# LED_PROGECT_SCH.net
KiCad netlist of a schematic drawn in Altium Designer
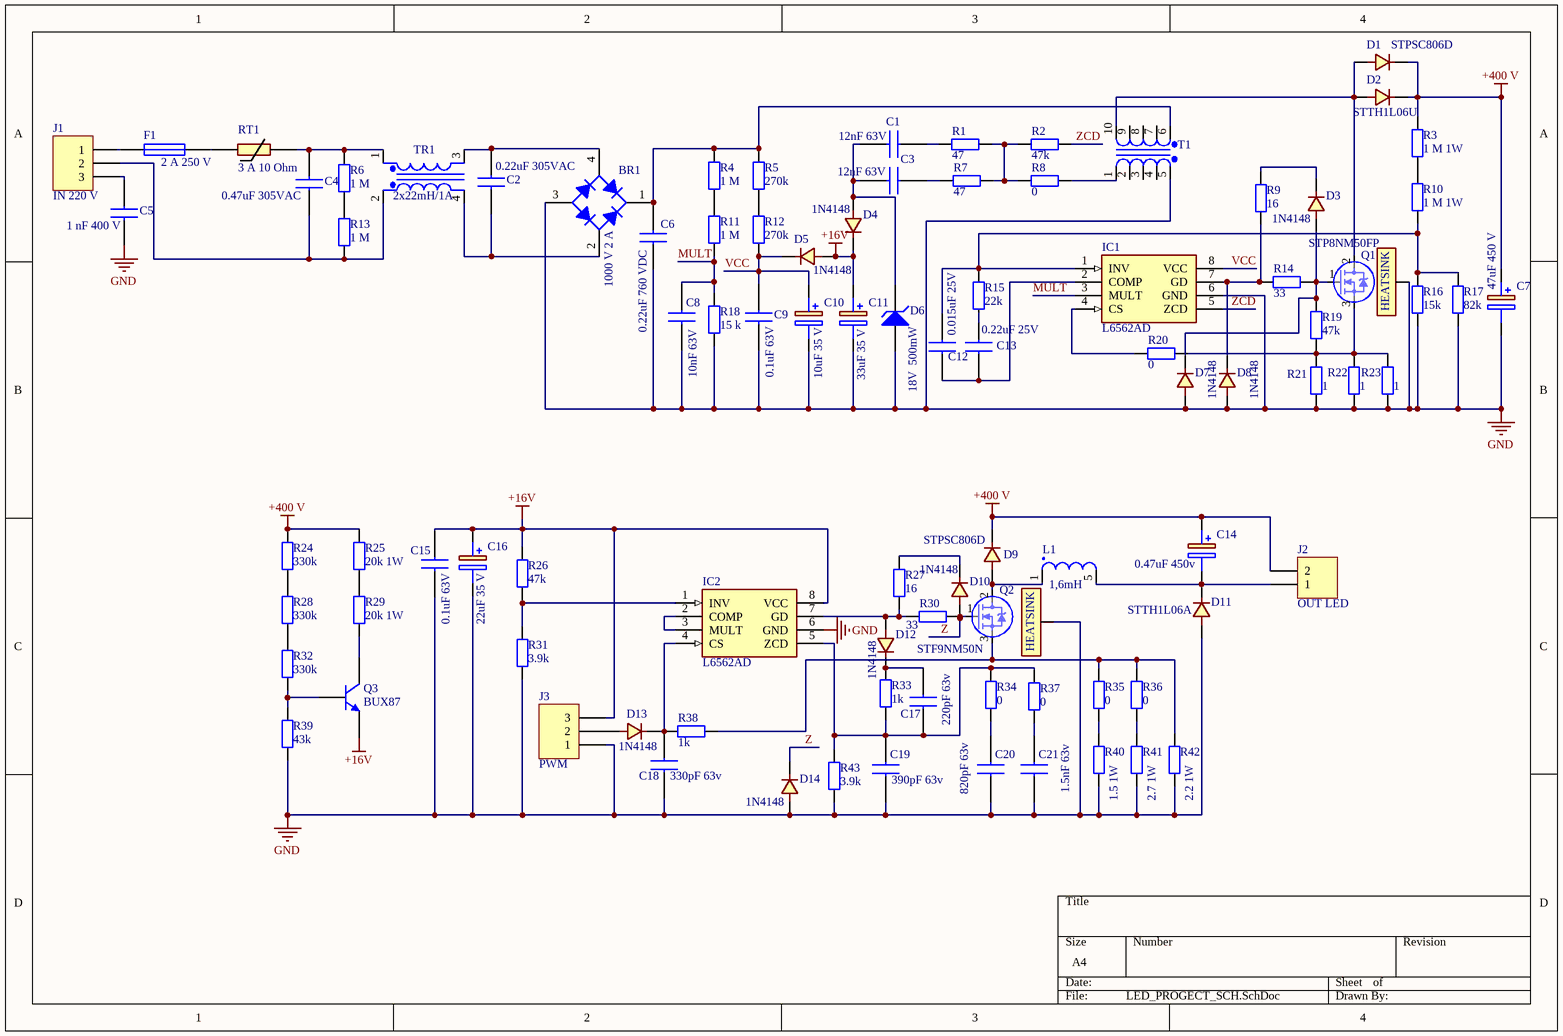
[diagram p0: LED_PROGECT_SCH.SchDoc]

(export (version "E")
  (design (tool "Eeschema 10.0.6"))
  (components
    (comp (ref "BR1")
      (value "1000 V 2 A")
      (footprint "SOPA-4")
      (description "Full Wave Diode Bridge")
      (fields (field (name "PUBLISHER") "Altium Limited"))
      (libsource (lib "Miscellaneous Devices") (part "Bridge1"))
    )
    (comp (ref "C1")
      (value "12nF 63V")
      (footprint "Cap1206")
      (description "Ceramic capacitor")
      (libsource (lib "SamacSys") (part "Capacotor 1206"))
    )
    (comp (ref "C2")
      (value "0.22uF 305VAC")
      (footprint "CAP32229")
      (description "Capacitor film")
      (libsource (lib "SamacSys") (part "Capacitor B32922"))
    )
    (comp (ref "C3")
      (value "12nF 63V")
      (footprint "Cap1206")
      (description "Ceramic capacitor")
      (libsource (lib "SamacSys") (part "Capacotor 1206"))
    )
    (comp (ref "C4")
      (value "0.47uF 305VAC")
      (footprint "CAP32229")
      (description "Capacitor film")
      (libsource (lib "SamacSys") (part "Capacitor B32922"))
    )
    (comp (ref "C5")
      (value "1 nF 400 V")
      (footprint "Capacitor radial")
      (description "Capacitor radial")
      (libsource (lib "SamacSys") (part "Capacitor C911U102MVWDBA7317"))
    )
    (comp (ref "C6")
      (value "0.22uF 760 VDC")
      (footprint "CAP32229")
      (description "Capacitor film")
      (libsource (lib "SamacSys") (part "Capacitor B32922"))
    )
    (comp (ref "C7")
      (value "47uF 450 V")
      (footprint "CAP ALUMINIUM 16 mm 1")
      (description "Cap polarized")
      (libsource (lib "SamacSys") (part "CAP POLARIZES 16-31 mm"))
    )
    (comp (ref "C8")
      (value "10nF 63V")
      (footprint "Cap1206")
      (description "Ceramic capacitor")
      (libsource (lib "SamacSys") (part "Capacotor 1206"))
    )
    (comp (ref "C9")
      (value "0.1uF 63V")
      (footprint "Cap1206")
      (description "Ceramic capacitor")
      (libsource (lib "SamacSys") (part "Capacotor 1206"))
    )
    (comp (ref "C10")
      (value "10uF 35 V")
      (footprint "CAP ALUM 5mm")
      (description "Cap polarized")
      (libsource (lib "SamacSys") (part "CAP POLARIZES 5-2 mm"))
    )
    (comp (ref "C11")
      (value "33uF 35 V")
      (footprint "CAP ALUM 5mm")
      (description "Cap polarized")
      (libsource (lib "SamacSys") (part "CAP POLARIZES 5-2 mm"))
    )
    (comp (ref "C12")
      (value "0.015uF 25V")
      (footprint "Cap1206")
      (description "Ceramic capacitor")
      (libsource (lib "SamacSys") (part "Capacotor 1206"))
    )
    (comp (ref "C13")
      (value "0.22uF 25V")
      (footprint "Cap1206")
      (description "Ceramic capacitor")
      (libsource (lib "SamacSys") (part "Capacotor 1206"))
    )
    (comp (ref "C14")
      (value "0.47uF 450v")
      (footprint "Cap aluminium 12.5x5")
      (description "Capacitpr polarized")
      (libsource (lib "SamacSys") (part "ESMG451ELLR47MJC5S"))
    )
    (comp (ref "C15")
      (value "0.1uF 63V")
      (footprint "Cap1206")
      (description "Ceramic capacitor")
      (libsource (lib "SamacSys") (part "Capacotor 1206"))
    )
    (comp (ref "C16")
      (value "22uF 35 V")
      (footprint "CAP ALUM 5mm")
      (description "Cap polarized")
      (libsource (lib "SamacSys") (part "CAP POLARIZES 5-2 mm"))
    )
    (comp (ref "C17")
      (value "220pF 63v")
      (footprint "CAP0805")
      (description "Ceramic capacitor")
      (libsource (lib "SamacSys") (part "Capacotor ceramic"))
    )
    (comp (ref "C18")
      (value "330pF 63v")
      (footprint "Cap1206")
      (description "Ceramic capacitor")
      (libsource (lib "SamacSys") (part "Capacotor 1206"))
    )
    (comp (ref "C19")
      (value "390pF 63v")
      (footprint "Cap1206")
      (description "Ceramic capacitor")
      (libsource (lib "SamacSys") (part "Capacotor 1206"))
    )
    (comp (ref "C20")
      (value "820pF 63v")
      (footprint "Cap1206")
      (description "Ceramic capacitor")
      (libsource (lib "SamacSys") (part "Capacotor 1206"))
    )
    (comp (ref "C21")
      (value "1.5nF 63v")
      (footprint "Cap1206")
      (description "Ceramic capacitor")
      (libsource (lib "SamacSys") (part "Capacotor 1206"))
    )
    (comp (ref "D1")
      (value "STPSC806D")
      (footprint "TO220 DOIDE")
      (description "600 V, 5 A")
      (libsource (lib "SamacSys") (part "STPSC806D"))
    )
    (comp (ref "D2")
      (value "STTH1L06U")
      (footprint "SMB")
      (description "600 V 1 A")
      (libsource (lib "SamacSys") (part "STTH1L06U"))
    )
    (comp (ref "D3")
      (value "1N4148")
      (footprint "SOD123")
      (description "Diode")
      (libsource (lib "SamacSys") (part "1N4148"))
    )
    (comp (ref "D4")
      (value "1N4148")
      (footprint "SOD123")
      (description "Diode")
      (libsource (lib "SamacSys") (part "1N4148"))
    )
    (comp (ref "D5")
      (value "1N4148")
      (footprint "SOD123")
      (description "Diode")
      (libsource (lib "SamacSys") (part "1N4148"))
    )
    (comp (ref "D6")
      (value "18V  500mW")
      (footprint "SOD123")
      (description "Diode Zener")
      (libsource (lib "SamacSys") (part "BZT52C18-7-F"))
    )
    (comp (ref "D7")
      (value "1N4148")
      (footprint "SOD123")
      (description "Diode")
      (libsource (lib "SamacSys") (part "1N4148"))
    )
    (comp (ref "D8")
      (value "1N4148")
      (footprint "SOD123")
      (description "Diode")
      (libsource (lib "SamacSys") (part "1N4148"))
    )
    (comp (ref "D9")
      (value "STPSC806D")
      (footprint "TO220 DOIDE")
      (description "600 V, 5 A")
      (libsource (lib "SamacSys") (part "STPSC806D"))
    )
    (comp (ref "D10")
      (value "1N4148")
      (footprint "SOD123")
      (description "Diode")
      (libsource (lib "SamacSys") (part "1N4148"))
    )
    (comp (ref "D11")
      (value "STTH1L06A")
      (footprint "SMA")
      (description "600 V ,1 A")
      (libsource (lib "SamacSys") (part "STTH1L06A"))
    )
    (comp (ref "D12")
      (value "1N4148")
      (footprint "SOD123")
      (description "Diode")
      (libsource (lib "SamacSys") (part "1N4148"))
    )
    (comp (ref "D13")
      (value "1N4148")
      (footprint "SOD123")
      (description "Diode")
      (libsource (lib "SamacSys") (part "1N4148"))
    )
    (comp (ref "D14")
      (value "1N4148")
      (footprint "SOD123")
      (description "Diode")
      (libsource (lib "SamacSys") (part "1N4148"))
    )
    (comp (ref "F1")
      (value "2 A 250 V")
      (footprint "FUSE SMD")
      (description "Fuse")
      (fields (field (name "PUBLISHER") "Altium Limited"))
      (libsource (lib "Miscellaneous Devices") (part "Fuse 1"))
    )
    (comp (ref "H1") (value "HEATSINK") (footprint "HEATSINK") (libsource (lib "SamacSys") (part "HEATSINK")))
    (comp (ref "H2") (value "HEATSINK") (footprint "HEATSINK") (libsource (lib "SamacSys") (part "HEATSINK")))
    (comp (ref "IC1")
      (value "L6562AD")
      (footprint "SOIC127P600X175-8N")
      (libsource (lib "SamacSys") (part "L6562AD"))
    )
    (comp (ref "IC2")
      (value "L6562AD")
      (footprint "SOIC127P600X175-8N")
      (libsource (lib "SamacSys") (part "L6562AD"))
    )
    (comp (ref "J1")
      (value "IN 220 V")
      (footprint "PIN3 TERMINAL")
      (libsource (lib "") (part "PIN3 TERMINAL 5 mm_1"))
    )
    (comp (ref "J2")
      (value "OUT LED")
      (footprint "TERMINAL 2 PIN")
      (libsource (lib "Miscellaneous Connectors") (part "PIN 2 TERMINAL"))
    )
    (comp (ref "J3")
      (value "PWM")
      (footprint "PIN3 TERMINAL")
      (libsource (lib "Miscellaneous Connectors") (part "PIN3 TERMINAL 5 mm"))
    )
    (comp (ref "L1")
      (value "1,6mH")
      (footprint "INDUCTOR E25/13/7")
      (description "INDUCTOR")
      (libsource (lib "Miscellaneous Devices") (part "INDUCTOR E25/13/7"))
    )
    (comp (ref "Q1")
      (value "STP8NM50FP")
      (footprint "TO220")
      (description "N-channel 500 V, 0.73 Ω typ., 5 A")
      (libsource (lib "SamacSys") (part "STD8NM50N"))
    )
    (comp (ref "Q2")
      (value "STF9NM50N")
      (footprint "TO220")
      (description "N-channel 500 V, 0.73 Ω typ., 5 A")
      (libsource (lib "SamacSys") (part "STD8NM50N"))
    )
    (comp (ref "Q3")
      (value "BUX87")
      (footprint "SOT32")
      (description "NPN power transistor")
      (libsource (lib "SamacSys") (part "BUX87"))
    )
    (comp (ref "R1")
      (value "47")
      (footprint "RES1206")
      (description "Resistor 1206")
      (libsource (lib "") (part "RES1206_2"))
    )
    (comp (ref "R2")
      (value "47k")
      (footprint "RES1206")
      (description "Resistor 1206")
      (libsource (lib "") (part "RES1206_2"))
    )
    (comp (ref "R3")
      (value "1 M 1W")
      (footprint "AXIAL-0.6")
      (description "Resistor")
      (fields (field (name "PUBLISHER") "Altium Limited"))
      (libsource (lib "Miscellaneous Devices") (part "Res 1W"))
    )
    (comp (ref "R4")
      (value "1 M")
      (footprint "RES1206")
      (description "Resistor 1206")
      (libsource (lib "") (part "RES1206_1"))
    )
    (comp (ref "R5")
      (value "270k")
      (footprint "RES1206")
      (description "Resistor 1206")
      (libsource (lib "") (part "RES1206_1"))
    )
    (comp (ref "R6")
      (value "1 M")
      (footprint "RES1206")
      (description "Resistor 1206")
      (libsource (lib "") (part "RES1206_1"))
    )
    (comp (ref "R7")
      (value "47")
      (footprint "RES1206")
      (description "Resistor 1206")
      (libsource (lib "") (part "RES1206_2"))
    )
    (comp (ref "R8")
      (value "0")
      (footprint "RES1206")
      (description "Resistor 1206")
      (libsource (lib "") (part "RES1206_2"))
    )
    (comp (ref "R9")
      (value "16")
      (footprint "RES1206")
      (description "Resistor 1206")
      (libsource (lib "") (part "RES1206_1"))
    )
    (comp (ref "R10")
      (value "1 M 1W")
      (footprint "AXIAL-0.6")
      (description "Resistor")
      (fields (field (name "PUBLISHER") "Altium Limited"))
      (libsource (lib "Miscellaneous Devices") (part "Res 1W"))
    )
    (comp (ref "R11")
      (value "1 M")
      (footprint "RES1206")
      (description "Resistor 1206")
      (libsource (lib "") (part "RES1206_1"))
    )
    (comp (ref "R12")
      (value "270k")
      (footprint "RES1206")
      (description "Resistor 1206")
      (libsource (lib "") (part "RES1206_1"))
    )
    (comp (ref "R13")
      (value "1 M")
      (footprint "RES1206")
      (description "Resistor 1206")
      (libsource (lib "") (part "RES1206_1"))
    )
    (comp (ref "R14")
      (value "33")
      (footprint "RES1206")
      (description "Resistor 1206")
      (libsource (lib "") (part "RES1206_3"))
    )
    (comp (ref "R15")
      (value "22k")
      (footprint "RES1206")
      (description "Resistor 1206")
      (libsource (lib "Miscellaneous Devices") (part "RES1206"))
    )
    (comp (ref "R16")
      (value "15k")
      (footprint "RES1206")
      (description "Resistor 1206")
      (libsource (lib "Miscellaneous Devices") (part "RES1206"))
    )
    (comp (ref "R17")
      (value "82k")
      (footprint "RES1206")
      (description "Resistor 1206")
      (libsource (lib "Miscellaneous Devices") (part "RES1206"))
    )
    (comp (ref "R18")
      (value "15 k")
      (footprint "RES1206")
      (description "Resistor 1206")
      (libsource (lib "") (part "RES1206_1"))
    )
    (comp (ref "R19")
      (value "47k")
      (footprint "RES1206")
      (description "Resistor 1206")
      (libsource (lib "") (part "RES1206_1"))
    )
    (comp (ref "R20")
      (value "0")
      (footprint "RES1206")
      (description "Resistor 1206")
      (libsource (lib "") (part "RES1206_2"))
    )
    (comp (ref "R21")
      (value "1")
      (footprint "RES1206")
      (description "Resistor 1206")
      (libsource (lib "") (part "RES1206_1"))
    )
    (comp (ref "R22")
      (value "1")
      (footprint "RES1206")
      (description "Resistor 1206")
      (libsource (lib "") (part "RES1206_1"))
    )
    (comp (ref "R23")
      (value "1")
      (footprint "RES1206")
      (description "Resistor 1206")
      (libsource (lib "") (part "RES1206_1"))
    )
    (comp (ref "R24")
      (value "330k")
      (footprint "RES1206")
      (description "Resistor 1206")
      (libsource (lib "") (part "RES1206_1"))
    )
    (comp (ref "R25")
      (value "20k 1W")
      (footprint "AXIAL-0.6")
      (description "Resistor")
      (fields (field (name "PUBLISHER") "Altium Limited"))
      (libsource (lib "Miscellaneous Devices") (part "Res 1W"))
    )
    (comp (ref "R26")
      (value "47k")
      (footprint "RES1206")
      (description "Resistor 1206")
      (libsource (lib "") (part "RES1206_1"))
    )
    (comp (ref "R27")
      (value "16")
      (footprint "RES1206")
      (description "Resistor 1206")
      (libsource (lib "") (part "RES1206_1"))
    )
    (comp (ref "R28")
      (value "330k")
      (footprint "RES1206")
      (description "Resistor 1206")
      (libsource (lib "") (part "RES1206_1"))
    )
    (comp (ref "R29")
      (value "20k 1W")
      (footprint "AXIAL-0.6")
      (description "Resistor")
      (fields (field (name "PUBLISHER") "Altium Limited"))
      (libsource (lib "Miscellaneous Devices") (part "Res 1W"))
    )
    (comp (ref "R30")
      (value "33")
      (footprint "RES1206")
      (description "Resistor 1206")
      (libsource (lib "") (part "RES1206_2"))
    )
    (comp (ref "R31")
      (value "3.9k")
      (footprint "RES1206")
      (description "Resistor 1206")
      (libsource (lib "") (part "RES1206_1"))
    )
    (comp (ref "R32")
      (value "330k")
      (footprint "RES1206")
      (description "Resistor 1206")
      (libsource (lib "") (part "RES1206_1"))
    )
    (comp (ref "R33")
      (value "1k")
      (footprint "RES1206")
      (description "Resistor 1206")
      (libsource (lib "Miscellaneous Devices") (part "RES1206"))
    )
    (comp (ref "R34")
      (value "0")
      (footprint "RES1206")
      (description "Resistor 1206")
      (libsource (lib "Miscellaneous Devices") (part "RES1206"))
    )
    (comp (ref "R35")
      (value "0")
      (footprint "RES1206")
      (description "Resistor 1206")
      (libsource (lib "Miscellaneous Devices") (part "RES1206"))
    )
    (comp (ref "R36")
      (value "0")
      (footprint "RES1206")
      (description "Resistor 1206")
      (libsource (lib "Miscellaneous Devices") (part "RES1206"))
    )
    (comp (ref "R37")
      (value "0")
      (footprint "RES1206")
      (description "Resistor 1206")
      (libsource (lib "Miscellaneous Devices") (part "RES1206"))
    )
    (comp (ref "R38")
      (value "1k")
      (footprint "RES1206")
      (description "Resistor 1206")
      (libsource (lib "") (part "RES1206_2"))
    )
    (comp (ref "R39")
      (value "43k")
      (footprint "RES1206")
      (description "Resistor 1206")
      (libsource (lib "") (part "RES1206_1"))
    )
    (comp (ref "R40")
      (value "1.5 1W")
      (footprint "AXIAL-0.6")
      (description "Resistor")
      (fields (field (name "PUBLISHER") "Altium Limited"))
      (libsource (lib "Miscellaneous Devices") (part "Res 1W"))
    )
    (comp (ref "R41")
      (value "2.7 1W")
      (footprint "AXIAL-0.6")
      (description "Resistor")
      (fields (field (name "PUBLISHER") "Altium Limited"))
      (libsource (lib "Miscellaneous Devices") (part "Res 1W"))
    )
    (comp (ref "R42")
      (value "2.2 1W")
      (footprint "AXIAL-0.6")
      (description "Resistor")
      (fields (field (name "PUBLISHER") "Altium Limited"))
      (libsource (lib "Miscellaneous Devices") (part "Res 1W"))
    )
    (comp (ref "R43")
      (value "3.9k")
      (footprint "RES1206")
      (description "Resistor 1206")
      (libsource (lib "Miscellaneous Devices") (part "RES1206"))
    )
    (comp (ref "RT1")
      (value "3 A 10 Ohm")
      (footprint "NTC")
      (description "Thermistor")
      (fields
        (field (name "MANUFACTURER_PART_NUMBER") "B57235S0100M051")
        (field (name "MOUSER PART NUMBER") "871-B57235S0100M051")
      )
      (libsource (lib "SamacSys") (part "B57235S0100M051"))
    )
    (comp (ref "T1")
      (value "Trans E25/13/7")
      (footprint "TRANS E25/13/7")
      (description "Center-Tapped Transformer (Coupled Inductor Model)")
      (fields (field (name "PUBLISHER") "Altium Limited"))
      (libsource (lib "Miscellaneous Devices") (part "Trans E25/13/7"))
    )
    (comp (ref "TR1")
      (value "2x22mH/1A")
      (footprint "CHOKE IND")
      (description "CHOKE")
      (libsource (lib "Miscellaneous Devices") (part "CHOKES 22uH 1A"))
    )
  )
  (nets
    (net (code "1") (name "+16V") (class "Default")
      (node (ref "C11") (pin "1") (pinfunction "+_1") (pintype "passive"))
      (node (ref "C15") (pin "2") (pinfunction "2_2") (pintype "passive"))
      (node (ref "C16") (pin "1") (pinfunction "+_1") (pintype "passive"))
      (node (ref "D4") (pin "2") (pinfunction "2_2") (pintype "passive"))
      (node (ref "D5") (pin "1") (pinfunction "1_1") (pintype "passive"))
      (node (ref "IC2") (pin "8") (pinfunction "VCC_8") (pintype "power_in"))
      (node (ref "J3") (pin "3") (pinfunction "3_3") (pintype "passive"))
      (node (ref "Q3") (pin "1") (pinfunction "E_1") (pintype "passive"))
      (node (ref "R26") (pin "2") (pinfunction "2_2") (pintype "passive"))
    )
    (net (code "2") (name "+400 V") (class "Default")
      (node (ref "C14") (pin "1") (pinfunction "+_1") (pintype "passive"))
      (node (ref "C7") (pin "1") (pinfunction "1_1") (pintype "passive"))
      (node (ref "D1") (pin "1") (pinfunction "1_1") (pintype "passive"))
      (node (ref "D2") (pin "2") (pinfunction "2_2") (pintype "passive"))
      (node (ref "D9") (pin "1") (pinfunction "1_1") (pintype "passive"))
      (node (ref "J2") (pin "2") (pinfunction "2_2") (pintype "passive"))
      (node (ref "R24") (pin "2") (pinfunction "2_2") (pintype "passive"))
      (node (ref "R25") (pin "2") (pinfunction "2_2") (pintype "passive"))
      (node (ref "R3") (pin "2") (pinfunction "2_2") (pintype "passive"))
    )
    (net (code "3") (name "/MULT") (class "Default")
      (node (ref "C8") (pin "2") (pinfunction "2_2") (pintype "passive"))
      (node (ref "IC1") (pin "3") (pinfunction "MULT_3") (pintype "passive"))
      (node (ref "R11") (pin "1") (pinfunction "1_1") (pintype "passive"))
      (node (ref "R18") (pin "2") (pinfunction "2_2") (pintype "passive"))
    )
    (net (code "4") (name "/VCC") (class "Default")
      (node (ref "C10") (pin "1") (pinfunction "+_1") (pintype "passive"))
      (node (ref "C9") (pin "2") (pinfunction "2_2") (pintype "passive"))
      (node (ref "D5") (pin "2") (pinfunction "2_2") (pintype "passive"))
      (node (ref "IC1") (pin "8") (pinfunction "VCC_8") (pintype "power_in"))
      (node (ref "R12") (pin "1") (pinfunction "1_1") (pintype "passive"))
    )
    (net (code "5") (name "/Z") (class "Default")
      (node (ref "D10") (pin "1") (pinfunction "1_1") (pintype "passive"))
      (node (ref "D14") (pin "2") (pinfunction "2_2") (pintype "passive"))
      (node (ref "Q2") (pin "1") (pinfunction "G_1") (pintype "passive"))
      (node (ref "R30") (pin "1") (pinfunction "1_1") (pintype "passive"))
    )
    (net (code "6") (name "/ZCD") (class "Default")
      (node (ref "IC1") (pin "5") (pinfunction "ZCD_5") (pintype "passive"))
      (node (ref "R2") (pin "1") (pinfunction "1_1") (pintype "passive"))
    )
    (net (code "7") (name "GND") (class "Default")
      (node (ref "BR1") (pin "3") (pinfunction "A_3") (pintype "passive"))
      (node (ref "C10") (pin "2") (pinfunction "-_2") (pintype "passive"))
      (node (ref "C11") (pin "2") (pinfunction "-_2") (pintype "passive"))
      (node (ref "C15") (pin "1") (pinfunction "1_1") (pintype "passive"))
      (node (ref "C16") (pin "2") (pinfunction "-_2") (pintype "passive"))
      (node (ref "C18") (pin "1") (pinfunction "1_1") (pintype "passive"))
      (node (ref "C19") (pin "1") (pinfunction "1_1") (pintype "passive"))
      (node (ref "C20") (pin "1") (pinfunction "1_1") (pintype "passive"))
      (node (ref "C21") (pin "1") (pinfunction "1_1") (pintype "passive"))
      (node (ref "C5") (pin "1") (pinfunction "1_1") (pintype "passive"))
      (node (ref "C6") (pin "1") (pinfunction "1_1") (pintype "passive"))
      (node (ref "C7") (pin "2") (pinfunction "2_2") (pintype "passive"))
      (node (ref "C8") (pin "1") (pinfunction "1_1") (pintype "passive"))
      (node (ref "C9") (pin "1") (pinfunction "1_1") (pintype "passive"))
      (node (ref "D11") (pin "1") (pinfunction "1_1") (pintype "passive"))
      (node (ref "D14") (pin "1") (pinfunction "1_1") (pintype "passive"))
      (node (ref "D6") (pin "1") (pinfunction "A_1") (pintype "passive"))
      (node (ref "D7") (pin "1") (pinfunction "1_1") (pintype "passive"))
      (node (ref "D8") (pin "1") (pinfunction "1_1") (pintype "passive"))
      (node (ref "H1") (pin "1") (pinfunction "C_1") (pintype "power_in"))
      (node (ref "H2") (pin "1") (pinfunction "C_1") (pintype "power_in"))
      (node (ref "IC1") (pin "6") (pinfunction "GND_6") (pintype "power_in"))
      (node (ref "IC2") (pin "6") (pinfunction "GND_6") (pintype "power_in"))
      (node (ref "J3") (pin "1") (pinfunction "1_1") (pintype "passive"))
      (node (ref "R16") (pin "2") (pinfunction "2_2") (pintype "passive"))
      (node (ref "R17") (pin "2") (pinfunction "2_2") (pintype "passive"))
      (node (ref "R18") (pin "1") (pinfunction "1_1") (pintype "passive"))
      (node (ref "R21") (pin "1") (pinfunction "1_1") (pintype "passive"))
      (node (ref "R22") (pin "1") (pinfunction "1_1") (pintype "passive"))
      (node (ref "R23") (pin "1") (pinfunction "1_1") (pintype "passive"))
      (node (ref "R31") (pin "1") (pinfunction "1_1") (pintype "passive"))
      (node (ref "R39") (pin "1") (pinfunction "1_1") (pintype "passive"))
      (node (ref "R40") (pin "1") (pinfunction "1_1") (pintype "passive"))
      (node (ref "R41") (pin "1") (pinfunction "1_1") (pintype "passive"))
      (node (ref "R42") (pin "1") (pinfunction "1_1") (pintype "passive"))
      (node (ref "R43") (pin "2") (pinfunction "2_2") (pintype "passive"))
      (node (ref "T1") (pin "5") (pinfunction "5_5") (pintype "passive"))
    )
    (net (code "8") (name "Net-(BR1-K)") (class "Default")
      (node (ref "BR1") (pin "1") (pinfunction "K_1") (pintype "passive"))
      (node (ref "C6") (pin "2") (pinfunction "2_2") (pintype "passive"))
      (node (ref "R4") (pin "2") (pinfunction "2_2") (pintype "passive"))
      (node (ref "R5") (pin "2") (pinfunction "2_2") (pintype "passive"))
      (node (ref "T1") (pin "6") (pinfunction "6_6") (pintype "passive"))
    )
    (net (code "9") (name "Net-(C1-Pad1)") (class "Default")
      (node (ref "C1") (pin "1") (pinfunction "1_1") (pintype "passive"))
      (node (ref "R1") (pin "2") (pinfunction "2_2") (pintype "passive"))
    )
    (net (code "10") (name "Net-(C3-Pad1)") (class "Default")
      (node (ref "C3") (pin "1") (pinfunction "1_1") (pintype "passive"))
      (node (ref "R7") (pin "2") (pinfunction "2_2") (pintype "passive"))
    )
    (net (code "11") (name "Net-(C5-Pad2)") (class "Default")
      (node (ref "C5") (pin "2") (pinfunction "2_2") (pintype "passive"))
      (node (ref "J1") (pin "3") (pinfunction "3_3") (pintype "passive"))
    )
    (net (code "12") (name "Net-(C13-Pad1)") (class "Default")
      (node (ref "C13") (pin "1") (pinfunction "1_1") (pintype "passive"))
      (node (ref "R15") (pin "2") (pinfunction "2_2") (pintype "passive"))
    )
    (net (code "13") (name "Net-(C14--)") (class "Default")
      (node (ref "C14") (pin "2") (pinfunction "-_2") (pintype "passive"))
      (node (ref "D11") (pin "2") (pinfunction "2_2") (pintype "passive"))
      (node (ref "J2") (pin "1") (pinfunction "1_1") (pintype "passive"))
      (node (ref "L1") (pin "5") (pinfunction "5_5") (pintype "passive"))
    )
    (net (code "14") (name "Net-(C17-Pad2)") (class "Default")
      (node (ref "C17") (pin "2") (pinfunction "2_2") (pintype "passive"))
      (node (ref "D12") (pin "2") (pinfunction "2_2") (pintype "passive"))
      (node (ref "R33") (pin "1") (pinfunction "1_1") (pintype "passive"))
    )
    (net (code "15") (name "Net-(C20-Pad2)") (class "Default")
      (node (ref "C20") (pin "2") (pinfunction "2_2") (pintype "passive"))
      (node (ref "R34") (pin "2") (pinfunction "2_2") (pintype "passive"))
    )
    (net (code "16") (name "Net-(C21-Pad2)") (class "Default")
      (node (ref "C21") (pin "2") (pinfunction "2_2") (pintype "passive"))
      (node (ref "R37") (pin "2") (pinfunction "2_2") (pintype "passive"))
    )
    (net (code "17") (name "Net-(D3-Pad2)") (class "Default")
      (node (ref "D3") (pin "2") (pinfunction "2_2") (pintype "passive"))
      (node (ref "R9") (pin "2") (pinfunction "2_2") (pintype "passive"))
    )
    (net (code "18") (name "Net-(D6-K)") (class "Default")
      (node (ref "C1") (pin "2") (pinfunction "2_2") (pintype "passive"))
      (node (ref "C3") (pin "2") (pinfunction "2_2") (pintype "passive"))
      (node (ref "D4") (pin "1") (pinfunction "1_1") (pintype "passive"))
      (node (ref "D6") (pin "2") (pinfunction "K_2") (pintype "passive"))
    )
    (net (code "19") (name "Net-(D10-Pad2)") (class "Default")
      (node (ref "D10") (pin "2") (pinfunction "2_2") (pintype "passive"))
      (node (ref "R27") (pin "2") (pinfunction "2_2") (pintype "passive"))
    )
    (net (code "20") (name "Net-(D13-Pad1)") (class "Default")
      (node (ref "D13") (pin "1") (pinfunction "1_1") (pintype "passive"))
      (node (ref "J3") (pin "2") (pinfunction "2_2") (pintype "passive"))
    )
    (net (code "21") (name "Net-(F1-Pad1)") (class "Default")
      (node (ref "F1") (pin "1") (pinfunction "1_1") (pintype "passive"))
      (node (ref "J1") (pin "1") (pinfunction "1_1") (pintype "passive"))
    )
    (net (code "22") (name "Net-(F1-Pad2)") (class "Default")
      (node (ref "F1") (pin "2") (pinfunction "2_2") (pintype "passive"))
      (node (ref "RT1") (pin "1") (pinfunction "1_1") (pintype "passive"))
    )
    (net (code "23") (name "Net-(IC1-COMP)") (class "Default")
      (node (ref "C12") (pin "2") (pinfunction "2_2") (pintype "passive"))
      (node (ref "C13") (pin "2") (pinfunction "2_2") (pintype "passive"))
      (node (ref "IC1") (pin "2") (pinfunction "COMP_2") (pintype "passive"))
    )
    (net (code "24") (name "Net-(IC1-CS)") (class "Default")
      (node (ref "IC1") (pin "4") (pinfunction "CS_4") (pintype "input"))
      (node (ref "R20") (pin "2") (pinfunction "2_2") (pintype "passive"))
    )
    (net (code "25") (name "Net-(IC1-GD)") (class "Default")
      (node (ref "D8") (pin "2") (pinfunction "2_2") (pintype "passive"))
      (node (ref "IC1") (pin "7") (pinfunction "GD_7") (pintype "passive"))
      (node (ref "R14") (pin "1") (pinfunction "1_1") (pintype "passive"))
      (node (ref "R9") (pin "1") (pinfunction "1_1") (pintype "passive"))
    )
    (net (code "26") (name "Net-(IC1-INV)") (class "Default")
      (node (ref "C12") (pin "1") (pinfunction "1_1") (pintype "passive"))
      (node (ref "IC1") (pin "1") (pinfunction "INV_1") (pintype "input"))
      (node (ref "R10") (pin "1") (pinfunction "1_1") (pintype "passive"))
      (node (ref "R15") (pin "1") (pinfunction "1_1") (pintype "passive"))
      (node (ref "R16") (pin "1") (pinfunction "1_1") (pintype "passive"))
      (node (ref "R17") (pin "1") (pinfunction "1_1") (pintype "passive"))
    )
    (net (code "27") (name "Net-(IC2-COMP)") (class "Default")
      (node (ref "IC2") (pin "2") (pinfunction "COMP_2") (pintype "passive"))
      (node (ref "IC2") (pin "3") (pinfunction "MULT_3") (pintype "passive"))
    )
    (net (code "28") (name "Net-(IC2-CS)") (class "Default")
      (node (ref "C18") (pin "2") (pinfunction "2_2") (pintype "passive"))
      (node (ref "D13") (pin "2") (pinfunction "2_2") (pintype "passive"))
      (node (ref "IC2") (pin "4") (pinfunction "CS_4") (pintype "input"))
      (node (ref "R38") (pin "2") (pinfunction "2_2") (pintype "passive"))
    )
    (net (code "29") (name "Net-(IC2-GD)") (class "Default")
      (node (ref "D12") (pin "1") (pinfunction "1_1") (pintype "passive"))
      (node (ref "IC2") (pin "7") (pinfunction "GD_7") (pintype "passive"))
      (node (ref "R27") (pin "1") (pinfunction "1_1") (pintype "passive"))
      (node (ref "R30") (pin "2") (pinfunction "2_2") (pintype "passive"))
    )
    (net (code "30") (name "Net-(IC2-INV)") (class "Default")
      (node (ref "IC2") (pin "1") (pinfunction "INV_1") (pintype "input"))
      (node (ref "R26") (pin "1") (pinfunction "1_1") (pintype "passive"))
      (node (ref "R31") (pin "2") (pinfunction "2_2") (pintype "passive"))
    )
    (net (code "31") (name "Net-(IC2-ZCD)") (class "Default")
      (node (ref "C17") (pin "1") (pinfunction "1_1") (pintype "passive"))
      (node (ref "C19") (pin "2") (pinfunction "2_2") (pintype "passive"))
      (node (ref "IC2") (pin "5") (pinfunction "ZCD_5") (pintype "passive"))
      (node (ref "R33") (pin "2") (pinfunction "2_2") (pintype "passive"))
      (node (ref "R34") (pin "1") (pinfunction "1_1") (pintype "passive"))
      (node (ref "R37") (pin "1") (pinfunction "1_1") (pintype "passive"))
      (node (ref "R43") (pin "1") (pinfunction "1_1") (pintype "passive"))
    )
    (net (code "32") (name "Net-(Q1-D)") (class "Default")
      (node (ref "D1") (pin "2") (pinfunction "2_2") (pintype "passive"))
      (node (ref "D2") (pin "1") (pinfunction "1_1") (pintype "passive"))
      (node (ref "Q1") (pin "2") (pinfunction "D_2") (pintype "passive"))
      (node (ref "T1") (pin "10") (pinfunction "10_10") (pintype "passive"))
    )
    (net (code "33") (name "Net-(Q1-G)") (class "Default")
      (node (ref "D3") (pin "1") (pinfunction "1_1") (pintype "passive"))
      (node (ref "D7") (pin "2") (pinfunction "2_2") (pintype "passive"))
      (node (ref "Q1") (pin "1") (pinfunction "G_1") (pintype "passive"))
      (node (ref "R14") (pin "2") (pinfunction "2_2") (pintype "passive"))
      (node (ref "R19") (pin "2") (pinfunction "2_2") (pintype "passive"))
    )
    (net (code "34") (name "Net-(Q1-S)") (class "Default")
      (node (ref "Q1") (pin "3") (pinfunction "S_3") (pintype "passive"))
      (node (ref "R19") (pin "1") (pinfunction "1_1") (pintype "passive"))
      (node (ref "R20") (pin "1") (pinfunction "1_1") (pintype "passive"))
      (node (ref "R21") (pin "2") (pinfunction "2_2") (pintype "passive"))
      (node (ref "R22") (pin "2") (pinfunction "2_2") (pintype "passive"))
      (node (ref "R23") (pin "2") (pinfunction "2_2") (pintype "passive"))
    )
    (net (code "35") (name "Net-(Q2-D)") (class "Default")
      (node (ref "D9") (pin "2") (pinfunction "2_2") (pintype "passive"))
      (node (ref "L1") (pin "1") (pinfunction "1_1") (pintype "passive"))
      (node (ref "Q2") (pin "2") (pinfunction "D_2") (pintype "passive"))
    )
    (net (code "36") (name "Net-(Q2-S)") (class "Default")
      (node (ref "Q2") (pin "3") (pinfunction "S_3") (pintype "passive"))
      (node (ref "R35") (pin "1") (pinfunction "1_1") (pintype "passive"))
      (node (ref "R36") (pin "1") (pinfunction "1_1") (pintype "passive"))
      (node (ref "R38") (pin "1") (pinfunction "1_1") (pintype "passive"))
      (node (ref "R42") (pin "2") (pinfunction "2_2") (pintype "passive"))
    )
    (net (code "37") (name "Net-(Q3-B)") (class "Default")
      (node (ref "Q3") (pin "3") (pinfunction "B_3") (pintype "passive"))
      (node (ref "R32") (pin "1") (pinfunction "1_1") (pintype "passive"))
      (node (ref "R39") (pin "2") (pinfunction "2_2") (pintype "passive"))
    )
    (net (code "38") (name "Net-(Q3-C)") (class "Default")
      (node (ref "Q3") (pin "2") (pinfunction "C_2") (pintype "passive"))
      (node (ref "R29") (pin "1") (pinfunction "1_1") (pintype "passive"))
    )
    (net (code "39") (name "Net-(R1-Pad1)") (class "Default")
      (node (ref "R1") (pin "1") (pinfunction "1_1") (pintype "passive"))
      (node (ref "R2") (pin "2") (pinfunction "2_2") (pintype "passive"))
      (node (ref "R7") (pin "1") (pinfunction "1_1") (pintype "passive"))
      (node (ref "R8") (pin "2") (pinfunction "2_2") (pintype "passive"))
    )
    (net (code "40") (name "Net-(R8-Pad1)") (class "Default")
      (node (ref "R8") (pin "1") (pinfunction "1_1") (pintype "passive"))
      (node (ref "T1") (pin "1") (pinfunction "1_1") (pintype "passive"))
    )
    (net (code "41") (name "Net-(R10-Pad2)") (class "Default")
      (node (ref "R10") (pin "2") (pinfunction "2_2") (pintype "passive"))
      (node (ref "R3") (pin "1") (pinfunction "1_1") (pintype "passive"))
    )
    (net (code "42") (name "Net-(R11-Pad2)") (class "Default")
      (node (ref "R11") (pin "2") (pinfunction "2_2") (pintype "passive"))
      (node (ref "R4") (pin "1") (pinfunction "1_1") (pintype "passive"))
    )
    (net (code "43") (name "Net-(R12-Pad2)") (class "Default")
      (node (ref "R12") (pin "2") (pinfunction "2_2") (pintype "passive"))
      (node (ref "R5") (pin "1") (pinfunction "1_1") (pintype "passive"))
    )
    (net (code "44") (name "Net-(R13-Pad2)") (class "Default")
      (node (ref "R13") (pin "2") (pinfunction "2_2") (pintype "passive"))
      (node (ref "R6") (pin "1") (pinfunction "1_1") (pintype "passive"))
    )
    (net (code "45") (name "Net-(R24-Pad1)") (class "Default")
      (node (ref "R24") (pin "1") (pinfunction "1_1") (pintype "passive"))
      (node (ref "R28") (pin "2") (pinfunction "2_2") (pintype "passive"))
    )
    (net (code "46") (name "Net-(R25-Pad1)") (class "Default")
      (node (ref "R25") (pin "1") (pinfunction "1_1") (pintype "passive"))
      (node (ref "R29") (pin "2") (pinfunction "2_2") (pintype "passive"))
    )
    (net (code "47") (name "Net-(R28-Pad1)") (class "Default")
      (node (ref "R28") (pin "1") (pinfunction "1_1") (pintype "passive"))
      (node (ref "R32") (pin "2") (pinfunction "2_2") (pintype "passive"))
    )
    (net (code "48") (name "Net-(R35-Pad2)") (class "Default")
      (node (ref "R35") (pin "2") (pinfunction "2_2") (pintype "passive"))
      (node (ref "R40") (pin "2") (pinfunction "2_2") (pintype "passive"))
    )
    (net (code "49") (name "Net-(R36-Pad2)") (class "Default")
      (node (ref "R36") (pin "2") (pinfunction "2_2") (pintype "passive"))
      (node (ref "R41") (pin "2") (pinfunction "2_2") (pintype "passive"))
    )
    (net (code "50") (name "Net-(TR1-Pri+)") (class "Default")
      (node (ref "C4") (pin "1") (pinfunction "1_1") (pintype "passive"))
      (node (ref "J1") (pin "2") (pinfunction "2_2") (pintype "passive"))
      (node (ref "R13") (pin "1") (pinfunction "1_1") (pintype "passive"))
      (node (ref "TR1") (pin "2") (pinfunction "Pri+_2") (pintype "passive"))
    )
    (net (code "51") (name "Net-(TR1-Pri-)") (class "Default")
      (node (ref "BR1") (pin "2") (pinfunction "C_2") (pintype "passive"))
      (node (ref "C2") (pin "1") (pinfunction "1_1") (pintype "passive"))
      (node (ref "TR1") (pin "4") (pinfunction "Pri-_4") (pintype "passive"))
    )
    (net (code "52") (name "Net-(TR1-Sec+)") (class "Default")
      (node (ref "C4") (pin "2") (pinfunction "2_2") (pintype "passive"))
      (node (ref "R6") (pin "2") (pinfunction "2_2") (pintype "passive"))
      (node (ref "RT1") (pin "2") (pinfunction "2_2") (pintype "passive"))
      (node (ref "TR1") (pin "1") (pinfunction "Sec+_1") (pintype "passive"))
    )
    (net (code "53") (name "Net-(TR1-Sec-)") (class "Default")
      (node (ref "BR1") (pin "4") (pinfunction "C_4") (pintype "passive"))
      (node (ref "C2") (pin "2") (pinfunction "2_2") (pintype "passive"))
      (node (ref "TR1") (pin "3") (pinfunction "Sec-_3") (pintype "passive"))
    )
    (net (code "54") (name "unconnected-(T1-Pad2)") (class "Default")
      (node (ref "T1") (pin "2") (pinfunction "2_2") (pintype "passive"))
    )
    (net (code "55") (name "unconnected-(T1-Pad3)") (class "Default")
      (node (ref "T1") (pin "3") (pinfunction "3_3") (pintype "passive"))
    )
    (net (code "56") (name "unconnected-(T1-Pad4)") (class "Default")
      (node (ref "T1") (pin "4") (pinfunction "4_4") (pintype "passive"))
    )
    (net (code "57") (name "unconnected-(T1-Pad7)") (class "Default")
      (node (ref "T1") (pin "7") (pinfunction "7_7") (pintype "passive"))
    )
    (net (code "58") (name "unconnected-(T1-Pad8)") (class "Default")
      (node (ref "T1") (pin "8") (pinfunction "8_8") (pintype "passive"))
    )
    (net (code "59") (name "unconnected-(T1-Pad9)") (class "Default")
      (node (ref "T1") (pin "9") (pinfunction "9_9") (pintype "passive"))
    )
  )
)
